# 07_-_FPGA_IO.net
KiCad netlist of a schematic drawn in Altium Designer
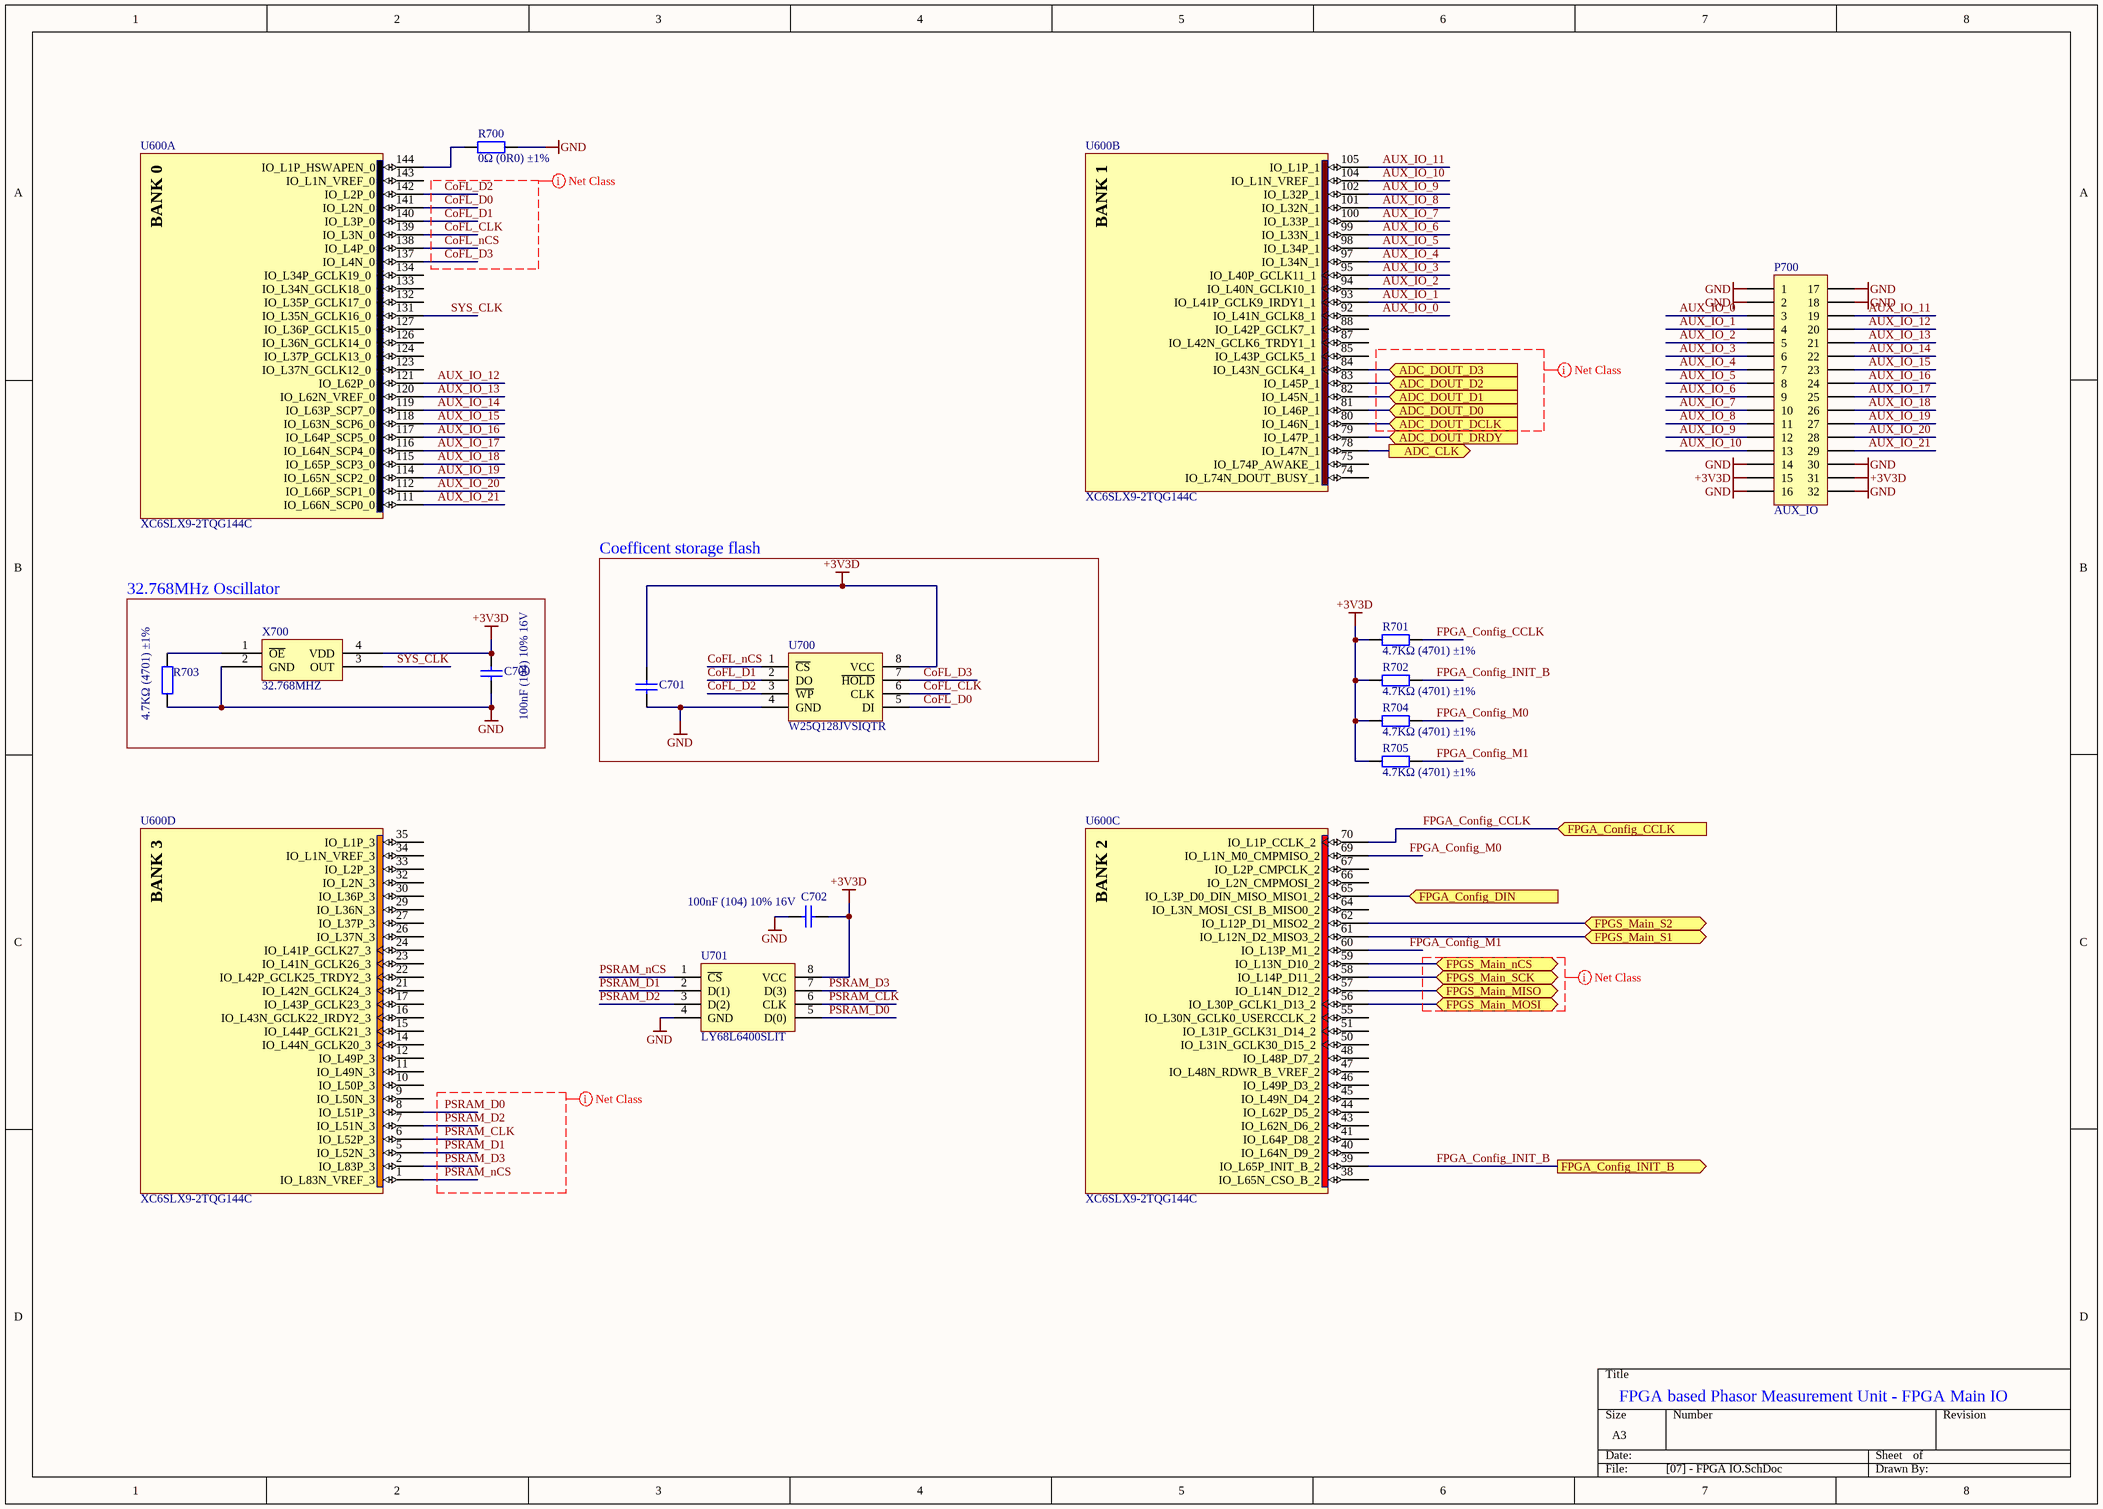
[diagram p0: [07] - FPGA IO.SchDoc]

(export (version "E")
  (design (tool "Eeschema 10.0.6"))
  (components
    (comp (ref "C700")
      (value "100nF (104) 10% 16V")
      (footprint "0402_C")
      (description "贴片电容")
      (libsource (lib "Cap") (part "0402 100nF (104) 10% 16V"))
    )
    (comp (ref "C701")
      (value "100nF (104) 10% 16V")
      (footprint "0402_C")
      (description "贴片电容")
      (libsource (lib "Cap") (part "0402 100nF (104) 10% 16V"))
    )
    (comp (ref "C702")
      (value "100nF (104) 10% 16V")
      (footprint "0402_C")
      (description "贴片电容")
      (libsource (lib "Cap") (part "0402 100nF (104) 10% 16V"))
    )
    (comp (ref "P700")
      (value "AUX_IO")
      (footprint "HDR2X16_CEN")
      (description "Header, 16-Pin, Dual row")
      (fields (field (name "PUBLISHER") "Altium Limited"))
      (libsource (lib "Miscellaneous Connectors") (part "Header 16X2A"))
    )
    (comp (ref "R700")
      (value "0Ω (0R0) ±1%")
      (footprint "0402_R")
      (description "贴片电阻")
      (libsource (lib "RES") (part "0402 0Ω (0R0) 1%"))
    )
    (comp (ref "R701")
      (value "4.7KΩ (4701) ±1%")
      (footprint "0402_R")
      (description "贴片电阻")
      (libsource (lib "RES") (part "0402 4.7KΩ (4701) 1%"))
    )
    (comp (ref "R702")
      (value "4.7KΩ (4701) ±1%")
      (footprint "0402_R")
      (description "贴片电阻")
      (libsource (lib "RES") (part "0402 4.7KΩ (4701) 1%"))
    )
    (comp (ref "R703")
      (value "4.7KΩ (4701) ±1%")
      (footprint "0402_R")
      (description "贴片电阻")
      (libsource (lib "") (part "0402 4.7KΩ (4701) 1%_1"))
    )
    (comp (ref "R704")
      (value "4.7KΩ (4701) ±1%")
      (footprint "0402_R")
      (description "贴片电阻")
      (libsource (lib "RES") (part "0402 4.7KΩ (4701) 1%"))
    )
    (comp (ref "R705")
      (value "4.7KΩ (4701) ±1%")
      (footprint "0402_R")
      (description "贴片电阻")
      (libsource (lib "RES") (part "0402 4.7KΩ (4701) 1%"))
    )
    (comp (ref "U600")
      (value "XC6SLX9-2TQG144C")
      (footprint "TQG144_N")
      (libsource (lib "Altium Content Vault") (part "FPGA-XSP6-XC6SLX9-SQ144"))
    )
    (comp (ref "U700")
      (value "W25Q128JVSIQTR")
      (footprint "SOIC-8_208mil")
      (description "Flash ROM")
      (libsource (lib "IC") (part "W25Q128JVSIQTR_[C97521]"))
    )
    (comp (ref "U701")
      (value "LY68L6400SLIT")
      (footprint "SOIC-8_208mil")
      (description "Pseudo SRAM")
      (libsource (lib "FPGA_PMU_lib") (part "LY68L6400SLIT"))
    )
    (comp (ref "X700")
      (value "32.768MHZ")
      (footprint "7050 Clock")
      (description "SMD OSCILLATORS(XO) 32.768MHZ ±25PPM SMD-7050_4P ROHS")
      (libsource (lib "FPGA_PMU_lib") (part "OCETDLJANF-32.768MHZ"))
    )
  )
  (nets
    (net (code "1") (name "+3V3D") (class "Default")
      (node (ref "C700") (pin "2") (pinfunction "2_2") (pintype "passive"))
      (node (ref "C701") (pin "2") (pinfunction "2_2") (pintype "passive"))
      (node (ref "C702") (pin "1") (pinfunction "1_1") (pintype "passive"))
      (node (ref "P700") (pin "15") (pinfunction "15_15") (pintype "passive"))
      (node (ref "P700") (pin "31") (pinfunction "31_31") (pintype "passive"))
      (node (ref "R701") (pin "2") (pinfunction "2_2") (pintype "passive"))
      (node (ref "R702") (pin "2") (pinfunction "2_2") (pintype "passive"))
      (node (ref "R704") (pin "2") (pinfunction "2_2") (pintype "passive"))
      (node (ref "R705") (pin "2") (pinfunction "2_2") (pintype "passive"))
      (node (ref "U700") (pin "8") (pinfunction "VCC_8") (pintype "passive"))
      (node (ref "U701") (pin "8") (pinfunction "VCC_8") (pintype "passive"))
      (node (ref "X700") (pin "4") (pinfunction "VDD_4") (pintype "passive"))
    )
    (net (code "2") (name "/ADC_CLK") (class "Default")
      (node (ref "U600") (pin "78") (pinfunction "IO_L47N_1_78") (pintype "bidirectional"))
    )
    (net (code "3") (name "/ADC_DOUT_D0") (class "Default")
      (node (ref "U600") (pin "81") (pinfunction "IO_L46P_1_81") (pintype "bidirectional"))
    )
    (net (code "4") (name "/ADC_DOUT_D1") (class "Default")
      (node (ref "U600") (pin "82") (pinfunction "IO_L45N_1_82") (pintype "bidirectional"))
    )
    (net (code "5") (name "/ADC_DOUT_D2") (class "Default")
      (node (ref "U600") (pin "83") (pinfunction "IO_L45P_1_83") (pintype "bidirectional"))
    )
    (net (code "6") (name "/ADC_DOUT_D3") (class "Default")
      (node (ref "U600") (pin "84") (pinfunction "IO_L43N_GCLK4_1_84") (pintype "bidirectional"))
    )
    (net (code "7") (name "/ADC_DOUT_DCLK") (class "Default")
      (node (ref "U600") (pin "80") (pinfunction "IO_L46N_1_80") (pintype "bidirectional"))
    )
    (net (code "8") (name "/ADC_DOUT_DRDY") (class "Default")
      (node (ref "U600") (pin "79") (pinfunction "IO_L47P_1_79") (pintype "bidirectional"))
    )
    (net (code "9") (name "/AUX_IO_0") (class "Default")
      (node (ref "P700") (pin "3") (pinfunction "3_3") (pintype "passive"))
      (node (ref "U600") (pin "92") (pinfunction "IO_L41N_GCLK8_1_92") (pintype "bidirectional"))
    )
    (net (code "10") (name "/AUX_IO_1") (class "Default")
      (node (ref "P700") (pin "4") (pinfunction "4_4") (pintype "passive"))
      (node (ref "U600") (pin "93") (pinfunction "IO_L41P_GCLK9_IRDY1_1_93") (pintype "bidirectional"))
    )
    (net (code "11") (name "/AUX_IO_2") (class "Default")
      (node (ref "P700") (pin "5") (pinfunction "5_5") (pintype "passive"))
      (node (ref "U600") (pin "94") (pinfunction "IO_L40N_GCLK10_1_94") (pintype "bidirectional"))
    )
    (net (code "12") (name "/AUX_IO_3") (class "Default")
      (node (ref "P700") (pin "6") (pinfunction "6_6") (pintype "passive"))
      (node (ref "U600") (pin "95") (pinfunction "IO_L40P_GCLK11_1_95") (pintype "bidirectional"))
    )
    (net (code "13") (name "/AUX_IO_4") (class "Default")
      (node (ref "P700") (pin "7") (pinfunction "7_7") (pintype "passive"))
      (node (ref "U600") (pin "97") (pinfunction "IO_L34N_1_97") (pintype "bidirectional"))
    )
    (net (code "14") (name "/AUX_IO_5") (class "Default")
      (node (ref "P700") (pin "8") (pinfunction "8_8") (pintype "passive"))
      (node (ref "U600") (pin "98") (pinfunction "IO_L34P_1_98") (pintype "bidirectional"))
    )
    (net (code "15") (name "/AUX_IO_6") (class "Default")
      (node (ref "P700") (pin "9") (pinfunction "9_9") (pintype "passive"))
      (node (ref "U600") (pin "99") (pinfunction "IO_L33N_1_99") (pintype "bidirectional"))
    )
    (net (code "16") (name "/AUX_IO_7") (class "Default")
      (node (ref "P700") (pin "10") (pinfunction "10_10") (pintype "passive"))
      (node (ref "U600") (pin "100") (pinfunction "IO_L33P_1_100") (pintype "bidirectional"))
    )
    (net (code "17") (name "/AUX_IO_8") (class "Default")
      (node (ref "P700") (pin "11") (pinfunction "11_11") (pintype "passive"))
      (node (ref "U600") (pin "101") (pinfunction "IO_L32N_1_101") (pintype "bidirectional"))
    )
    (net (code "18") (name "/AUX_IO_9") (class "Default")
      (node (ref "P700") (pin "12") (pinfunction "12_12") (pintype "passive"))
      (node (ref "U600") (pin "102") (pinfunction "IO_L32P_1_102") (pintype "bidirectional"))
    )
    (net (code "19") (name "/AUX_IO_10") (class "Default")
      (node (ref "P700") (pin "13") (pinfunction "13_13") (pintype "passive"))
      (node (ref "U600") (pin "104") (pinfunction "IO_L1N_VREF_1_104") (pintype "bidirectional"))
    )
    (net (code "20") (name "/AUX_IO_11") (class "Default")
      (node (ref "P700") (pin "19") (pinfunction "19_19") (pintype "passive"))
      (node (ref "U600") (pin "105") (pinfunction "IO_L1P_1_105") (pintype "bidirectional"))
    )
    (net (code "21") (name "/AUX_IO_12") (class "Default")
      (node (ref "P700") (pin "20") (pinfunction "20_20") (pintype "passive"))
      (node (ref "U600") (pin "121") (pinfunction "IO_L62P_0_121") (pintype "bidirectional"))
    )
    (net (code "22") (name "/AUX_IO_13") (class "Default")
      (node (ref "P700") (pin "21") (pinfunction "21_21") (pintype "passive"))
      (node (ref "U600") (pin "120") (pinfunction "IO_L62N_VREF_0_120") (pintype "bidirectional"))
    )
    (net (code "23") (name "/AUX_IO_14") (class "Default")
      (node (ref "P700") (pin "22") (pinfunction "22_22") (pintype "passive"))
      (node (ref "U600") (pin "119") (pinfunction "IO_L63P_SCP7_0_119") (pintype "bidirectional"))
    )
    (net (code "24") (name "/AUX_IO_15") (class "Default")
      (node (ref "P700") (pin "23") (pinfunction "23_23") (pintype "passive"))
      (node (ref "U600") (pin "118") (pinfunction "IO_L63N_SCP6_0_118") (pintype "bidirectional"))
    )
    (net (code "25") (name "/AUX_IO_16") (class "Default")
      (node (ref "P700") (pin "24") (pinfunction "24_24") (pintype "passive"))
      (node (ref "U600") (pin "117") (pinfunction "IO_L64P_SCP5_0_117") (pintype "bidirectional"))
    )
    (net (code "26") (name "/AUX_IO_17") (class "Default")
      (node (ref "P700") (pin "25") (pinfunction "25_25") (pintype "passive"))
      (node (ref "U600") (pin "116") (pinfunction "IO_L64N_SCP4_0_116") (pintype "bidirectional"))
    )
    (net (code "27") (name "/AUX_IO_18") (class "Default")
      (node (ref "P700") (pin "26") (pinfunction "26_26") (pintype "passive"))
      (node (ref "U600") (pin "115") (pinfunction "IO_L65P_SCP3_0_115") (pintype "bidirectional"))
    )
    (net (code "28") (name "/AUX_IO_19") (class "Default")
      (node (ref "P700") (pin "27") (pinfunction "27_27") (pintype "passive"))
      (node (ref "U600") (pin "114") (pinfunction "IO_L65N_SCP2_0_114") (pintype "bidirectional"))
    )
    (net (code "29") (name "/AUX_IO_20") (class "Default")
      (node (ref "P700") (pin "28") (pinfunction "28_28") (pintype "passive"))
      (node (ref "U600") (pin "112") (pinfunction "IO_L66P_SCP1_0_112") (pintype "bidirectional"))
    )
    (net (code "30") (name "/AUX_IO_21") (class "Default")
      (node (ref "P700") (pin "29") (pinfunction "29_29") (pintype "passive"))
      (node (ref "U600") (pin "111") (pinfunction "IO_L66N_SCP0_0_111") (pintype "bidirectional"))
    )
    (net (code "31") (name "/CoFL_CLK") (class "Default")
      (node (ref "U600") (pin "139") (pinfunction "IO_L3N_0_139") (pintype "bidirectional"))
      (node (ref "U700") (pin "6") (pinfunction "CLK_6") (pintype "passive"))
    )
    (net (code "32") (name "/CoFL_D0") (class "Default")
      (node (ref "U600") (pin "141") (pinfunction "IO_L2N_0_141") (pintype "bidirectional"))
      (node (ref "U700") (pin "5") (pinfunction "DI_5") (pintype "passive"))
    )
    (net (code "33") (name "/CoFL_D1") (class "Default")
      (node (ref "U600") (pin "140") (pinfunction "IO_L3P_0_140") (pintype "bidirectional"))
      (node (ref "U700") (pin "2") (pinfunction "DO_2") (pintype "passive"))
    )
    (net (code "34") (name "/CoFL_D2") (class "Default")
      (node (ref "U600") (pin "142") (pinfunction "IO_L2P_0_142") (pintype "bidirectional"))
      (node (ref "U700") (pin "3") (pinfunction "~{WP}_3") (pintype "passive"))
    )
    (net (code "35") (name "/CoFL_D3") (class "Default")
      (node (ref "U600") (pin "137") (pinfunction "IO_L4N_0_137") (pintype "bidirectional"))
      (node (ref "U700") (pin "7") (pinfunction "~{HOLD}_7") (pintype "passive"))
    )
    (net (code "36") (name "/CoFL_nCS") (class "Default")
      (node (ref "U600") (pin "138") (pinfunction "IO_L4P_0_138") (pintype "bidirectional"))
      (node (ref "U700") (pin "1") (pinfunction "~{CS}_1") (pintype "passive"))
    )
    (net (code "37") (name "/FPGA_Config_CCLK") (class "Default")
      (node (ref "R701") (pin "1") (pinfunction "1_1") (pintype "passive"))
      (node (ref "U600") (pin "70") (pinfunction "IO_L1P_CCLK_2_70") (pintype "bidirectional"))
    )
    (net (code "38") (name "/FPGA_Config_DIN") (class "Default")
      (node (ref "U600") (pin "65") (pinfunction "IO_L3P_D0_DIN_MISO_MISO1_2_65") (pintype "bidirectional"))
    )
    (net (code "39") (name "/FPGA_Config_INIT_B") (class "Default")
      (node (ref "R702") (pin "1") (pinfunction "1_1") (pintype "passive"))
      (node (ref "U600") (pin "39") (pinfunction "IO_L65P_INIT_B_2_39") (pintype "bidirectional"))
    )
    (net (code "40") (name "/FPGA_Config_M0") (class "Default")
      (node (ref "R704") (pin "1") (pinfunction "1_1") (pintype "passive"))
      (node (ref "U600") (pin "69") (pinfunction "IO_L1N_M0_CMPMISO_2_69") (pintype "bidirectional"))
    )
    (net (code "41") (name "/FPGA_Config_M1") (class "Default")
      (node (ref "R705") (pin "1") (pinfunction "1_1") (pintype "passive"))
      (node (ref "U600") (pin "60") (pinfunction "IO_L13P_M1_2_60") (pintype "bidirectional"))
    )
    (net (code "42") (name "/FPGS_Main_MISO") (class "Default")
      (node (ref "U600") (pin "57") (pinfunction "IO_L14N_D12_2_57") (pintype "bidirectional"))
    )
    (net (code "43") (name "/FPGS_Main_MOSI") (class "Default")
      (node (ref "U600") (pin "56") (pinfunction "IO_L30P_GCLK1_D13_2_56") (pintype "bidirectional"))
    )
    (net (code "44") (name "/FPGS_Main_S1") (class "Default")
      (node (ref "U600") (pin "61") (pinfunction "IO_L12N_D2_MISO3_2_61") (pintype "bidirectional"))
    )
    (net (code "45") (name "/FPGS_Main_S2") (class "Default")
      (node (ref "U600") (pin "62") (pinfunction "IO_L12P_D1_MISO2_2_62") (pintype "bidirectional"))
    )
    (net (code "46") (name "/FPGS_Main_SCK") (class "Default")
      (node (ref "U600") (pin "58") (pinfunction "IO_L14P_D11_2_58") (pintype "bidirectional"))
    )
    (net (code "47") (name "/FPGS_Main_nCS") (class "Default")
      (node (ref "U600") (pin "59") (pinfunction "IO_L13N_D10_2_59") (pintype "bidirectional"))
    )
    (net (code "48") (name "/PSRAM_CLK") (class "Default")
      (node (ref "U600") (pin "6") (pinfunction "IO_L52P_3_6") (pintype "bidirectional"))
      (node (ref "U701") (pin "6") (pinfunction "CLK_6") (pintype "passive"))
    )
    (net (code "49") (name "/PSRAM_D0") (class "Default")
      (node (ref "U600") (pin "8") (pinfunction "IO_L51P_3_8") (pintype "bidirectional"))
      (node (ref "U701") (pin "5") (pinfunction "D(0)_5") (pintype "passive"))
    )
    (net (code "50") (name "/PSRAM_D1") (class "Default")
      (node (ref "U600") (pin "5") (pinfunction "IO_L52N_3_5") (pintype "bidirectional"))
      (node (ref "U701") (pin "2") (pinfunction "D(1)_2") (pintype "passive"))
    )
    (net (code "51") (name "/PSRAM_D2") (class "Default")
      (node (ref "U600") (pin "7") (pinfunction "IO_L51N_3_7") (pintype "bidirectional"))
      (node (ref "U701") (pin "3") (pinfunction "D(2)_3") (pintype "passive"))
    )
    (net (code "52") (name "/PSRAM_D3") (class "Default")
      (node (ref "U600") (pin "2") (pinfunction "IO_L83P_3_2") (pintype "bidirectional"))
      (node (ref "U701") (pin "7") (pinfunction "D(3)_7") (pintype "passive"))
    )
    (net (code "53") (name "/PSRAM_nCS") (class "Default")
      (node (ref "U600") (pin "1") (pinfunction "IO_L83N_VREF_3_1") (pintype "bidirectional"))
      (node (ref "U701") (pin "1") (pinfunction "~{CS}_1") (pintype "passive"))
    )
    (net (code "54") (name "/SYS_CLK") (class "Default")
      (node (ref "U600") (pin "131") (pinfunction "IO_L35N_GCLK16_0_131") (pintype "bidirectional"))
      (node (ref "X700") (pin "3") (pinfunction "OUT_3") (pintype "passive"))
    )
    (net (code "55") (name "GND") (class "Default")
      (node (ref "C700") (pin "1") (pinfunction "1_1") (pintype "passive"))
      (node (ref "C701") (pin "1") (pinfunction "1_1") (pintype "passive"))
      (node (ref "C702") (pin "2") (pinfunction "2_2") (pintype "passive"))
      (node (ref "P700") (pin "1") (pinfunction "1_1") (pintype "passive"))
      (node (ref "P700") (pin "14") (pinfunction "14_14") (pintype "passive"))
      (node (ref "P700") (pin "16") (pinfunction "16_16") (pintype "passive"))
      (node (ref "P700") (pin "17") (pinfunction "17_17") (pintype "passive"))
      (node (ref "P700") (pin "18") (pinfunction "18_18") (pintype "passive"))
      (node (ref "P700") (pin "2") (pinfunction "2_2") (pintype "passive"))
      (node (ref "P700") (pin "30") (pinfunction "30_30") (pintype "passive"))
      (node (ref "P700") (pin "32") (pinfunction "32_32") (pintype "passive"))
      (node (ref "R700") (pin "2") (pinfunction "2_2") (pintype "passive"))
      (node (ref "R703") (pin "1") (pinfunction "1_1") (pintype "passive"))
      (node (ref "U700") (pin "4") (pinfunction "GND_4") (pintype "passive"))
      (node (ref "U701") (pin "4") (pinfunction "GND_4") (pintype "passive"))
      (node (ref "X700") (pin "2") (pinfunction "GND_2") (pintype "passive"))
    )
    (net (code "56") (name "Net-(U600A-IO_L1P_HSWAPEN_0)") (class "Default")
      (node (ref "R700") (pin "1") (pinfunction "1_1") (pintype "passive"))
      (node (ref "U600") (pin "144") (pinfunction "IO_L1P_HSWAPEN_0_144") (pintype "bidirectional"))
    )
    (net (code "57") (name "Net-(X700-~{OE})") (class "Default")
      (node (ref "R703") (pin "2") (pinfunction "2_2") (pintype "passive"))
      (node (ref "X700") (pin "1") (pinfunction "~{OE}_1") (pintype "passive"))
    )
    (net (code "58") (name "unconnected-(U600A-IO_L1N_VREF_0-Pad143)") (class "Default")
      (node (ref "U600") (pin "143") (pinfunction "IO_L1N_VREF_0_143") (pintype "bidirectional"))
    )
    (net (code "59") (name "unconnected-(U600A-IO_L34N_GCLK18_0-Pad133)") (class "Default")
      (node (ref "U600") (pin "133") (pinfunction "IO_L34N_GCLK18_0_133") (pintype "bidirectional"))
    )
    (net (code "60") (name "unconnected-(U600A-IO_L34P_GCLK19_0-Pad134)") (class "Default")
      (node (ref "U600") (pin "134") (pinfunction "IO_L34P_GCLK19_0_134") (pintype "bidirectional"))
    )
    (net (code "61") (name "unconnected-(U600A-IO_L35P_GCLK17_0-Pad132)") (class "Default")
      (node (ref "U600") (pin "132") (pinfunction "IO_L35P_GCLK17_0_132") (pintype "bidirectional"))
    )
    (net (code "62") (name "unconnected-(U600A-IO_L36N_GCLK14_0-Pad126)") (class "Default")
      (node (ref "U600") (pin "126") (pinfunction "IO_L36N_GCLK14_0_126") (pintype "bidirectional"))
    )
    (net (code "63") (name "unconnected-(U600A-IO_L36P_GCLK15_0-Pad127)") (class "Default")
      (node (ref "U600") (pin "127") (pinfunction "IO_L36P_GCLK15_0_127") (pintype "bidirectional"))
    )
    (net (code "64") (name "unconnected-(U600A-IO_L37N_GCLK12_0-Pad123)") (class "Default")
      (node (ref "U600") (pin "123") (pinfunction "IO_L37N_GCLK12_0_123") (pintype "bidirectional"))
    )
    (net (code "65") (name "unconnected-(U600A-IO_L37P_GCLK13_0-Pad124)") (class "Default")
      (node (ref "U600") (pin "124") (pinfunction "IO_L37P_GCLK13_0_124") (pintype "bidirectional"))
    )
    (net (code "66") (name "unconnected-(U600B-IO_L42N_GCLK6_TRDY1_1-Pad87)") (class "Default")
      (node (ref "U600") (pin "87") (pinfunction "IO_L42N_GCLK6_TRDY1_1_87") (pintype "bidirectional"))
    )
    (net (code "67") (name "unconnected-(U600B-IO_L42P_GCLK7_1-Pad88)") (class "Default")
      (node (ref "U600") (pin "88") (pinfunction "IO_L42P_GCLK7_1_88") (pintype "bidirectional"))
    )
    (net (code "68") (name "unconnected-(U600B-IO_L43P_GCLK5_1-Pad85)") (class "Default")
      (node (ref "U600") (pin "85") (pinfunction "IO_L43P_GCLK5_1_85") (pintype "bidirectional"))
    )
    (net (code "69") (name "unconnected-(U600B-IO_L74N_DOUT_BUSY_1-Pad74)") (class "Default")
      (node (ref "U600") (pin "74") (pinfunction "IO_L74N_DOUT_BUSY_1_74") (pintype "bidirectional"))
    )
    (net (code "70") (name "unconnected-(U600B-IO_L74P_AWAKE_1-Pad75)") (class "Default")
      (node (ref "U600") (pin "75") (pinfunction "IO_L74P_AWAKE_1_75") (pintype "bidirectional"))
    )
    (net (code "71") (name "unconnected-(U600C-IO_L2N_CMPMOSI_2-Pad66)") (class "Default")
      (node (ref "U600") (pin "66") (pinfunction "IO_L2N_CMPMOSI_2_66") (pintype "bidirectional"))
    )
    (net (code "72") (name "unconnected-(U600C-IO_L2P_CMPCLK_2-Pad67)") (class "Default")
      (node (ref "U600") (pin "67") (pinfunction "IO_L2P_CMPCLK_2_67") (pintype "bidirectional"))
    )
    (net (code "73") (name "unconnected-(U600C-IO_L3N_MOSI_CSI_B_MISO0_2-Pad64)") (class "Default")
      (node (ref "U600") (pin "64") (pinfunction "IO_L3N_MOSI_CSI_B_MISO0_2_64") (pintype "bidirectional"))
    )
    (net (code "74") (name "unconnected-(U600C-IO_L30N_GCLK0_USERCCLK_2-Pad55)") (class "Default")
      (node (ref "U600") (pin "55") (pinfunction "IO_L30N_GCLK0_USERCCLK_2_55") (pintype "bidirectional"))
    )
    (net (code "75") (name "unconnected-(U600C-IO_L31N_GCLK30_D15_2-Pad50)") (class "Default")
      (node (ref "U600") (pin "50") (pinfunction "IO_L31N_GCLK30_D15_2_50") (pintype "bidirectional"))
    )
    (net (code "76") (name "unconnected-(U600C-IO_L31P_GCLK31_D14_2-Pad51)") (class "Default")
      (node (ref "U600") (pin "51") (pinfunction "IO_L31P_GCLK31_D14_2_51") (pintype "bidirectional"))
    )
    (net (code "77") (name "unconnected-(U600C-IO_L48N_RDWR_B_VREF_2-Pad47)") (class "Default")
      (node (ref "U600") (pin "47") (pinfunction "IO_L48N_RDWR_B_VREF_2_47") (pintype "bidirectional"))
    )
    (net (code "78") (name "unconnected-(U600C-IO_L48P_D7_2-Pad48)") (class "Default")
      (node (ref "U600") (pin "48") (pinfunction "IO_L48P_D7_2_48") (pintype "bidirectional"))
    )
    (net (code "79") (name "unconnected-(U600C-IO_L49N_D4_2-Pad45)") (class "Default")
      (node (ref "U600") (pin "45") (pinfunction "IO_L49N_D4_2_45") (pintype "bidirectional"))
    )
    (net (code "80") (name "unconnected-(U600C-IO_L49P_D3_2-Pad46)") (class "Default")
      (node (ref "U600") (pin "46") (pinfunction "IO_L49P_D3_2_46") (pintype "bidirectional"))
    )
    (net (code "81") (name "unconnected-(U600C-IO_L62N_D6_2-Pad43)") (class "Default")
      (node (ref "U600") (pin "43") (pinfunction "IO_L62N_D6_2_43") (pintype "bidirectional"))
    )
    (net (code "82") (name "unconnected-(U600C-IO_L62P_D5_2-Pad44)") (class "Default")
      (node (ref "U600") (pin "44") (pinfunction "IO_L62P_D5_2_44") (pintype "bidirectional"))
    )
    (net (code "83") (name "unconnected-(U600C-IO_L64N_D9_2-Pad40)") (class "Default")
      (node (ref "U600") (pin "40") (pinfunction "IO_L64N_D9_2_40") (pintype "bidirectional"))
    )
    (net (code "84") (name "unconnected-(U600C-IO_L64P_D8_2-Pad41)") (class "Default")
      (node (ref "U600") (pin "41") (pinfunction "IO_L64P_D8_2_41") (pintype "bidirectional"))
    )
    (net (code "85") (name "unconnected-(U600C-IO_L65N_CSO_B_2-Pad38)") (class "Default")
      (node (ref "U600") (pin "38") (pinfunction "IO_L65N_CSO_B_2_38") (pintype "bidirectional"))
    )
    (net (code "86") (name "unconnected-(U600D-IO_L1N_VREF_3-Pad34)") (class "Default")
      (node (ref "U600") (pin "34") (pinfunction "IO_L1N_VREF_3_34") (pintype "bidirectional"))
    )
    (net (code "87") (name "unconnected-(U600D-IO_L1P_3-Pad35)") (class "Default")
      (node (ref "U600") (pin "35") (pinfunction "IO_L1P_3_35") (pintype "bidirectional"))
    )
    (net (code "88") (name "unconnected-(U600D-IO_L2N_3-Pad32)") (class "Default")
      (node (ref "U600") (pin "32") (pinfunction "IO_L2N_3_32") (pintype "bidirectional"))
    )
    (net (code "89") (name "unconnected-(U600D-IO_L2P_3-Pad33)") (class "Default")
      (node (ref "U600") (pin "33") (pinfunction "IO_L2P_3_33") (pintype "bidirectional"))
    )
    (net (code "90") (name "unconnected-(U600D-IO_L36N_3-Pad29)") (class "Default")
      (node (ref "U600") (pin "29") (pinfunction "IO_L36N_3_29") (pintype "bidirectional"))
    )
    (net (code "91") (name "unconnected-(U600D-IO_L36P_3-Pad30)") (class "Default")
      (node (ref "U600") (pin "30") (pinfunction "IO_L36P_3_30") (pintype "bidirectional"))
    )
    (net (code "92") (name "unconnected-(U600D-IO_L37N_3-Pad26)") (class "Default")
      (node (ref "U600") (pin "26") (pinfunction "IO_L37N_3_26") (pintype "bidirectional"))
    )
    (net (code "93") (name "unconnected-(U600D-IO_L37P_3-Pad27)") (class "Default")
      (node (ref "U600") (pin "27") (pinfunction "IO_L37P_3_27") (pintype "bidirectional"))
    )
    (net (code "94") (name "unconnected-(U600D-IO_L41N_GCLK26_3-Pad23)") (class "Default")
      (node (ref "U600") (pin "23") (pinfunction "IO_L41N_GCLK26_3_23") (pintype "bidirectional"))
    )
    (net (code "95") (name "unconnected-(U600D-IO_L41P_GCLK27_3-Pad24)") (class "Default")
      (node (ref "U600") (pin "24") (pinfunction "IO_L41P_GCLK27_3_24") (pintype "bidirectional"))
    )
    (net (code "96") (name "unconnected-(U600D-IO_L42N_GCLK24_3-Pad21)") (class "Default")
      (node (ref "U600") (pin "21") (pinfunction "IO_L42N_GCLK24_3_21") (pintype "bidirectional"))
    )
    (net (code "97") (name "unconnected-(U600D-IO_L42P_GCLK25_TRDY2_3-Pad22)") (class "Default")
      (node (ref "U600") (pin "22") (pinfunction "IO_L42P_GCLK25_TRDY2_3_22") (pintype "bidirectional"))
    )
    (net (code "98") (name "unconnected-(U600D-IO_L43N_GCLK22_IRDY2_3-Pad16)") (class "Default")
      (node (ref "U600") (pin "16") (pinfunction "IO_L43N_GCLK22_IRDY2_3_16") (pintype "bidirectional"))
    )
    (net (code "99") (name "unconnected-(U600D-IO_L43P_GCLK23_3-Pad17)") (class "Default")
      (node (ref "U600") (pin "17") (pinfunction "IO_L43P_GCLK23_3_17") (pintype "bidirectional"))
    )
    (net (code "100") (name "unconnected-(U600D-IO_L44N_GCLK20_3-Pad14)") (class "Default")
      (node (ref "U600") (pin "14") (pinfunction "IO_L44N_GCLK20_3_14") (pintype "bidirectional"))
    )
    (net (code "101") (name "unconnected-(U600D-IO_L44P_GCLK21_3-Pad15)") (class "Default")
      (node (ref "U600") (pin "15") (pinfunction "IO_L44P_GCLK21_3_15") (pintype "bidirectional"))
    )
    (net (code "102") (name "unconnected-(U600D-IO_L49N_3-Pad11)") (class "Default")
      (node (ref "U600") (pin "11") (pinfunction "IO_L49N_3_11") (pintype "bidirectional"))
    )
    (net (code "103") (name "unconnected-(U600D-IO_L49P_3-Pad12)") (class "Default")
      (node (ref "U600") (pin "12") (pinfunction "IO_L49P_3_12") (pintype "bidirectional"))
    )
    (net (code "104") (name "unconnected-(U600D-IO_L50N_3-Pad9)") (class "Default")
      (node (ref "U600") (pin "9") (pinfunction "IO_L50N_3_9") (pintype "bidirectional"))
    )
    (net (code "105") (name "unconnected-(U600D-IO_L50P_3-Pad10)") (class "Default")
      (node (ref "U600") (pin "10") (pinfunction "IO_L50P_3_10") (pintype "bidirectional"))
    )
  )
)
